# fet_iac.net
KiCad netlist of a schematic drawn in EAGLE
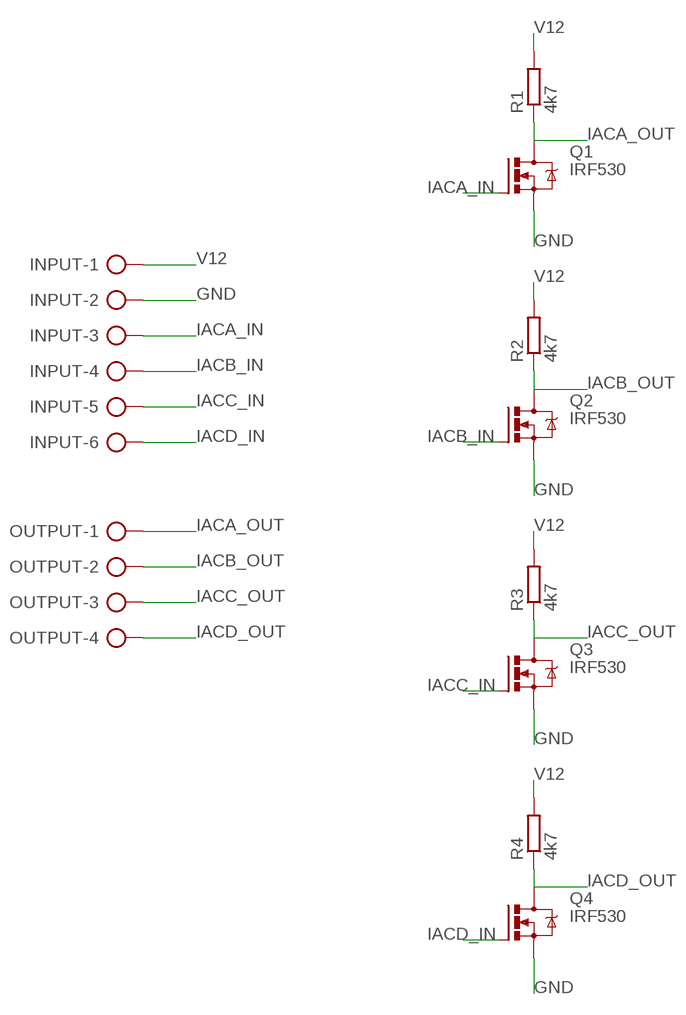
[diagram p0: schematic, sheet 1]

(export (version "E")
  (design (tool "Eeschema 10.0.6"))
  (components
    (comp (ref "INPUT")
      (value "AK500/6")
      (footprint "eagle-import:AK500_6")
      (libsource (lib "eagle-import") (part "AK500/6"))
    )
    (comp (ref "OUTPUT")
      (value "AK500/4")
      (footprint "eagle-import:AK500_4")
      (libsource (lib "eagle-import") (part "AK500/4"))
    )
    (comp (ref "Q1")
      (value "IRF530")
      (footprint "eagle-import:TO220BV")
      (libsource (lib "eagle-import") (part "IRF530"))
    )
    (comp (ref "Q2")
      (value "IRF530")
      (footprint "eagle-import:TO220BV")
      (libsource (lib "eagle-import") (part "IRF530"))
    )
    (comp (ref "Q3")
      (value "IRF530")
      (footprint "eagle-import:TO220BV")
      (libsource (lib "eagle-import") (part "IRF530"))
    )
    (comp (ref "Q4")
      (value "IRF530")
      (footprint "eagle-import:TO220BV")
      (libsource (lib "eagle-import") (part "IRF530"))
    )
    (comp (ref "R1")
      (value "4k7")
      (footprint "eagle-import:0204_7")
      (libsource (lib "eagle-import") (part "R-EU_0204/7"))
    )
    (comp (ref "R2")
      (value "4k7")
      (footprint "eagle-import:0204_7")
      (libsource (lib "eagle-import") (part "R-EU_0204/7"))
    )
    (comp (ref "R3")
      (value "4k7")
      (footprint "eagle-import:0204_7")
      (libsource (lib "eagle-import") (part "R-EU_0204/7"))
    )
    (comp (ref "R4")
      (value "4k7")
      (footprint "eagle-import:0204_7")
      (libsource (lib "eagle-import") (part "R-EU_0204/7"))
    )
  )
  (nets
    (net (code "1") (name "/GND") (class "Default")
      (node (ref "INPUT") (pin "2") (pinfunction "KL_2") (pintype "passive"))
      (node (ref "Q1") (pin "S") (pinfunction "S_S") (pintype "passive"))
      (node (ref "Q2") (pin "S") (pinfunction "S_S") (pintype "passive"))
      (node (ref "Q3") (pin "S") (pinfunction "S_S") (pintype "passive"))
      (node (ref "Q4") (pin "S") (pinfunction "S_S") (pintype "passive"))
    )
    (net (code "2") (name "/IACA_IN") (class "Default")
      (node (ref "INPUT") (pin "3") (pinfunction "KL_3") (pintype "passive"))
      (node (ref "Q1") (pin "G") (pinfunction "G_G") (pintype "passive"))
    )
    (net (code "3") (name "/IACA_OUT") (class "Default")
      (node (ref "OUTPUT") (pin "1") (pinfunction "KL_1") (pintype "passive"))
      (node (ref "Q1") (pin "D") (pinfunction "D_D") (pintype "passive"))
      (node (ref "R1") (pin "1") (pinfunction "1_1") (pintype "passive"))
    )
    (net (code "4") (name "/IACB_IN") (class "Default")
      (node (ref "INPUT") (pin "4") (pinfunction "KL_4") (pintype "passive"))
      (node (ref "Q2") (pin "G") (pinfunction "G_G") (pintype "passive"))
    )
    (net (code "5") (name "/IACB_OUT") (class "Default")
      (node (ref "OUTPUT") (pin "2") (pinfunction "KL_2") (pintype "passive"))
      (node (ref "Q2") (pin "D") (pinfunction "D_D") (pintype "passive"))
      (node (ref "R2") (pin "1") (pinfunction "1_1") (pintype "passive"))
    )
    (net (code "6") (name "/IACC_IN") (class "Default")
      (node (ref "INPUT") (pin "5") (pinfunction "KL_5") (pintype "passive"))
      (node (ref "Q3") (pin "G") (pinfunction "G_G") (pintype "passive"))
    )
    (net (code "7") (name "/IACC_OUT") (class "Default")
      (node (ref "OUTPUT") (pin "3") (pinfunction "KL_3") (pintype "passive"))
      (node (ref "Q3") (pin "D") (pinfunction "D_D") (pintype "passive"))
      (node (ref "R3") (pin "1") (pinfunction "1_1") (pintype "passive"))
    )
    (net (code "8") (name "/IACD_IN") (class "Default")
      (node (ref "INPUT") (pin "6") (pinfunction "KL_6") (pintype "passive"))
      (node (ref "Q4") (pin "G") (pinfunction "G_G") (pintype "passive"))
    )
    (net (code "9") (name "/IACD_OUT") (class "Default")
      (node (ref "OUTPUT") (pin "4") (pinfunction "KL_4") (pintype "passive"))
      (node (ref "Q4") (pin "D") (pinfunction "D_D") (pintype "passive"))
      (node (ref "R4") (pin "1") (pinfunction "1_1") (pintype "passive"))
    )
    (net (code "10") (name "/V12") (class "Default")
      (node (ref "INPUT") (pin "1") (pinfunction "KL_1") (pintype "passive"))
      (node (ref "R1") (pin "2") (pinfunction "2_2") (pintype "passive"))
      (node (ref "R2") (pin "2") (pinfunction "2_2") (pintype "passive"))
      (node (ref "R3") (pin "2") (pinfunction "2_2") (pintype "passive"))
      (node (ref "R4") (pin "2") (pinfunction "2_2") (pintype "passive"))
    )
  )
)
